# logo.net
KiCad netlist of a schematic drawn in EAGLE
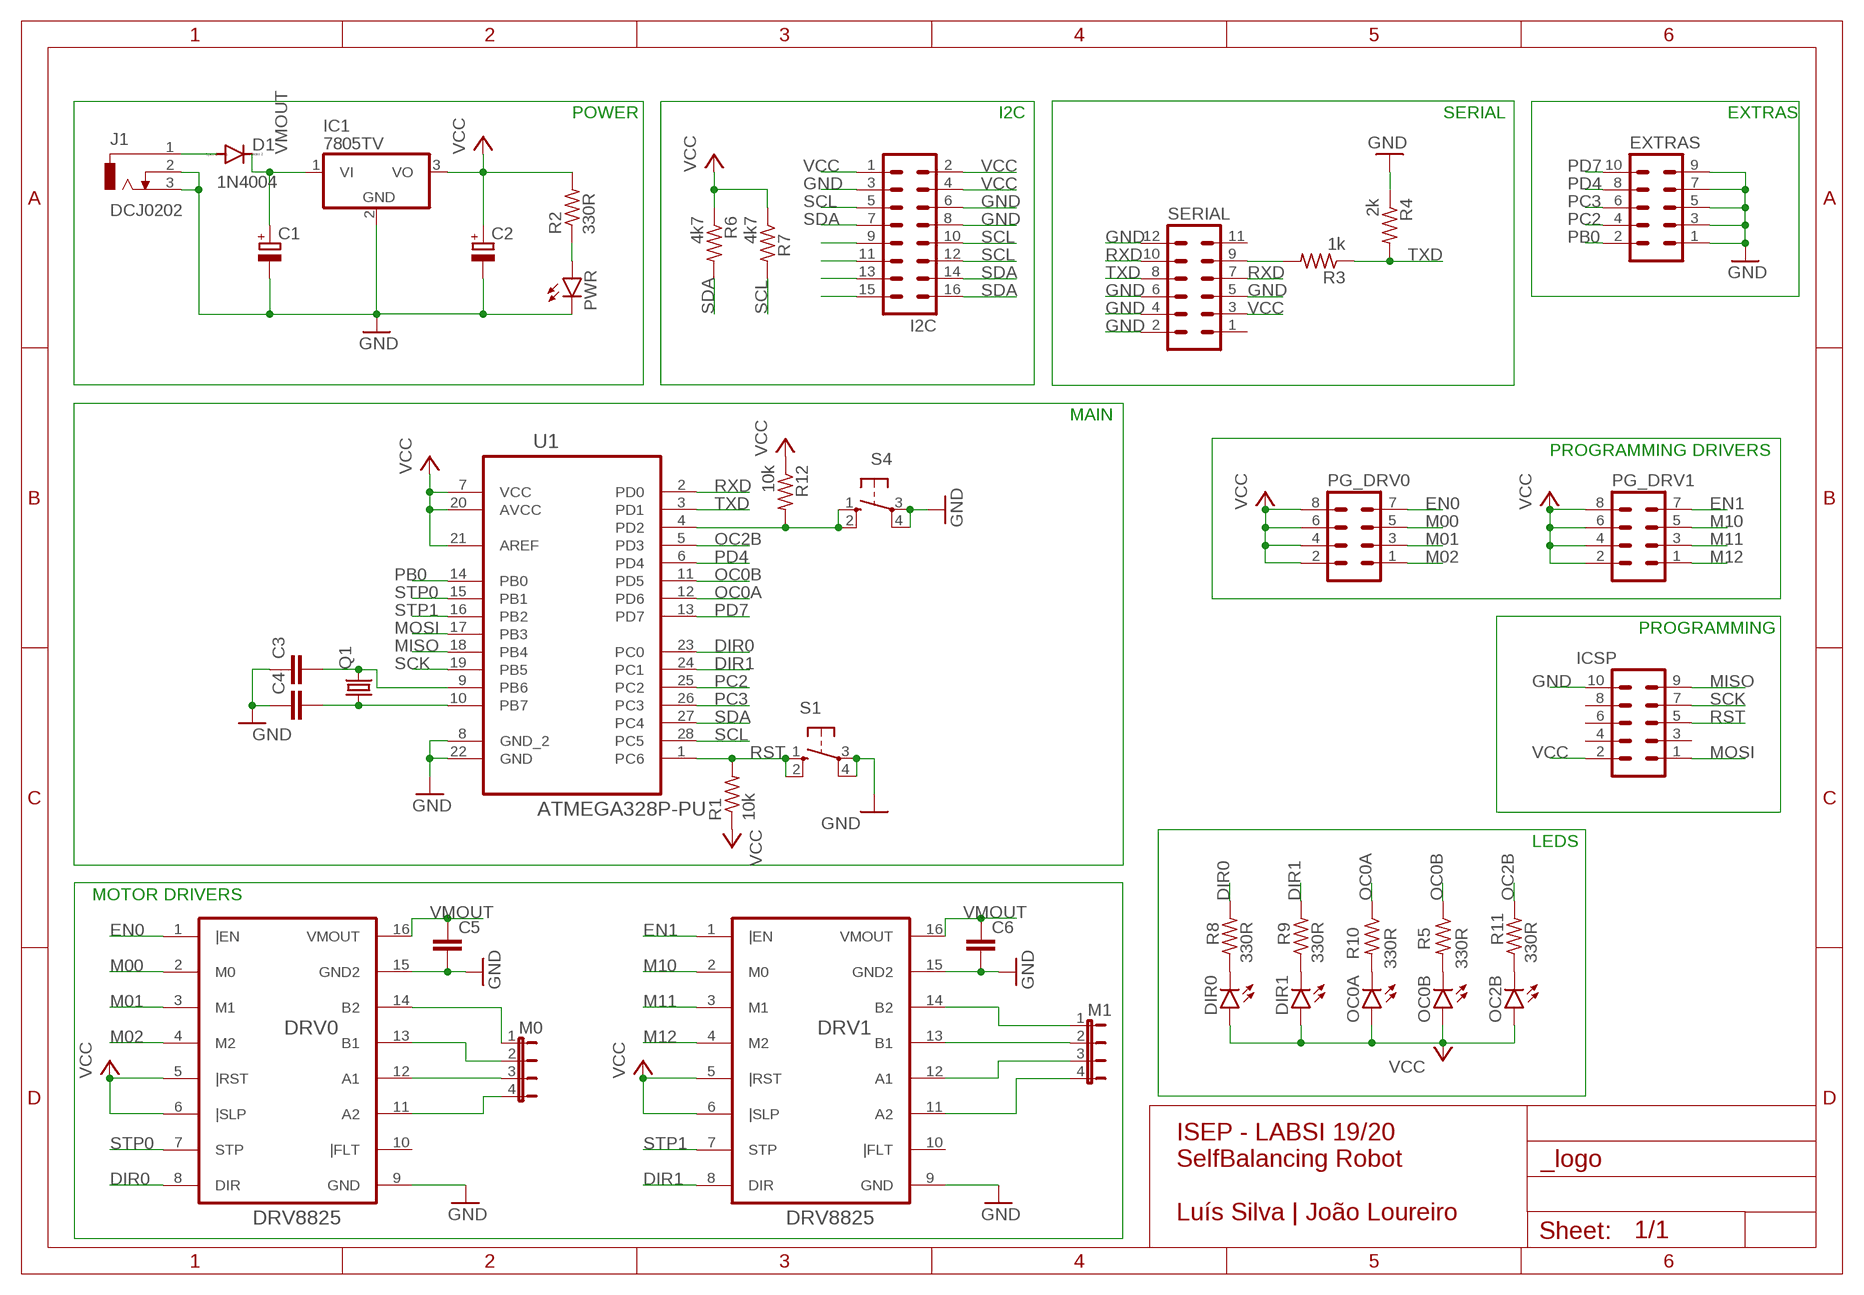
[diagram p0: schematic, sheet 1]

(export (version "E")
  (design (tool "Eeschema 10.0.6"))
  (components
    (comp (ref "C1")
      (value "CPOL-EUB45181A")
      (footprint "eagle-import:B45181A")
      (libsource (lib "eagle-import") (part "CPOL-EUB45181A"))
    )
    (comp (ref "C2")
      (value "CPOL-EUB45181A")
      (footprint "eagle-import:B45181A")
      (libsource (lib "eagle-import") (part "CPOL-EUB45181A"))
    )
    (comp (ref "C3")
      (value "C5/3")
      (footprint "eagle-import:C5B3")
      (libsource (lib "eagle-import") (part "C5/3"))
    )
    (comp (ref "C4")
      (value "C5/3")
      (footprint "eagle-import:C5B3")
      (libsource (lib "eagle-import") (part "C5/3"))
    )
    (comp (ref "C5")
      (value "C2.5/2")
      (footprint "eagle-import:C2.5-2")
      (libsource (lib "eagle-import") (part "C2.5/2"))
    )
    (comp (ref "C6")
      (value "C2.5/2")
      (footprint "eagle-import:C2.5-2")
      (libsource (lib "eagle-import") (part "C2.5/2"))
    )
    (comp (ref "D1")
      (value "1N4004")
      (footprint "eagle-import:DO41-10")
      (libsource (lib "eagle-import") (part "1N4004"))
    )
    (comp (ref "DIR0")
      (value "LED3MM")
      (footprint "eagle-import:LED3MM")
      (libsource (lib "eagle-import") (part "LED3MM"))
    )
    (comp (ref "DIR1")
      (value "LED3MM")
      (footprint "eagle-import:LED3MM")
      (libsource (lib "eagle-import") (part "LED3MM"))
    )
    (comp (ref "DRV0")
      (value "DRV8825")
      (footprint "eagle-import:DRV8825")
      (fields (field (name "MF") "Generic"))
      (libsource (lib "eagle-import") (part "DRV8825"))
    )
    (comp (ref "DRV1")
      (value "DRV8825")
      (footprint "eagle-import:DRV8825")
      (fields (field (name "MF") "Generic"))
      (libsource (lib "eagle-import") (part "DRV8825"))
    )
    (comp (ref "EXTRAS")
      (value "ML10")
      (footprint "eagle-import:ML10")
      (libsource (lib "eagle-import") (part "ML10"))
    )
    (comp (ref "I2C")
      (value "MA08-2")
      (footprint "eagle-import:MA08-2")
      (libsource (lib "eagle-import") (part "MA08-2"))
    )
    (comp (ref "IC1")
      (value "7805TV")
      (footprint "eagle-import:TO220V")
      (libsource (lib "eagle-import") (part "78TV05"))
    )
    (comp (ref "ICSP")
      (value "ML10")
      (footprint "eagle-import:ML10")
      (libsource (lib "eagle-import") (part "ML10"))
    )
    (comp (ref "J1")
      (value "DCJ0202")
      (footprint "eagle-import:DCJ0202")
      (libsource (lib "eagle-import") (part "DCJ0202"))
    )
    (comp (ref "M0")
      (value "JP4E")
      (footprint "eagle-import:JP4")
      (libsource (lib "eagle-import") (part "JP4E"))
    )
    (comp (ref "M1")
      (value "JP4E")
      (footprint "eagle-import:JP4")
      (libsource (lib "eagle-import") (part "JP4E"))
    )
    (comp (ref "OC0A")
      (value "LED3MM")
      (footprint "eagle-import:LED3MM")
      (libsource (lib "eagle-import") (part "LED3MM"))
    )
    (comp (ref "OC0B")
      (value "LED3MM")
      (footprint "eagle-import:LED3MM")
      (libsource (lib "eagle-import") (part "LED3MM"))
    )
    (comp (ref "OC2B")
      (value "LED3MM")
      (footprint "eagle-import:LED3MM")
      (libsource (lib "eagle-import") (part "LED3MM"))
    )
    (comp (ref "PG_DRV0")
      (value "MA04-2")
      (footprint "eagle-import:MA04-2")
      (libsource (lib "eagle-import") (part "MA04-2"))
    )
    (comp (ref "PG_DRV1")
      (value "MA04-2")
      (footprint "eagle-import:MA04-2")
      (libsource (lib "eagle-import") (part "MA04-2"))
    )
    (comp (ref "PWR")
      (value "LED3MM")
      (footprint "eagle-import:LED3MM")
      (libsource (lib "eagle-import") (part "LED3MM"))
    )
    (comp (ref "Q1")
      (value "CRYSTALHC49S")
      (footprint "eagle-import:HC49_S")
      (libsource (lib "eagle-import") (part "CRYSTALHC49S"))
    )
    (comp (ref "R1")
      (value "10k")
      (footprint "eagle-import:0207_10")
      (libsource (lib "eagle-import") (part "R-US_0207/10"))
    )
    (comp (ref "R2")
      (value "330R")
      (footprint "eagle-import:0207_10")
      (libsource (lib "eagle-import") (part "R-US_0207/10"))
    )
    (comp (ref "R3")
      (value "1k")
      (footprint "eagle-import:0207_10")
      (libsource (lib "eagle-import") (part "R-US_0207/10"))
    )
    (comp (ref "R4")
      (value "2k")
      (footprint "eagle-import:0207_10")
      (libsource (lib "eagle-import") (part "R-US_0207/10"))
    )
    (comp (ref "R5")
      (value "330R")
      (footprint "eagle-import:0207_10")
      (libsource (lib "eagle-import") (part "R-US_0207/10"))
    )
    (comp (ref "R6")
      (value "4k7")
      (footprint "eagle-import:0207_10")
      (libsource (lib "eagle-import") (part "R-US_0207/10"))
    )
    (comp (ref "R7")
      (value "4k7")
      (footprint "eagle-import:0207_10")
      (libsource (lib "eagle-import") (part "R-US_0207/10"))
    )
    (comp (ref "R8")
      (value "330R")
      (footprint "eagle-import:0207_10")
      (libsource (lib "eagle-import") (part "R-US_0207/10"))
    )
    (comp (ref "R9")
      (value "330R")
      (footprint "eagle-import:0207_10")
      (libsource (lib "eagle-import") (part "R-US_0207/10"))
    )
    (comp (ref "R10")
      (value "330R")
      (footprint "eagle-import:0207_10")
      (libsource (lib "eagle-import") (part "R-US_0207/10"))
    )
    (comp (ref "R11")
      (value "330R")
      (footprint "eagle-import:0207_10")
      (libsource (lib "eagle-import") (part "R-US_0207/10"))
    )
    (comp (ref "R12")
      (value "10k")
      (footprint "eagle-import:0207_10")
      (libsource (lib "eagle-import") (part "R-US_0207/10"))
    )
    (comp (ref "S1")
      (value "10-XX")
      (footprint "eagle-import:B3F-10XX")
      (fields (field (name "MPN") "B3F-1000"))
      (libsource (lib "eagle-import") (part "10-XX"))
    )
    (comp (ref "S4")
      (value "10-XX")
      (footprint "eagle-import:B3F-10XX")
      (fields (field (name "MPN") "B3F-1000"))
      (libsource (lib "eagle-import") (part "10-XX"))
    )
    (comp (ref "SERIAL")
      (value "MA06-2")
      (footprint "eagle-import:MA06-2")
      (libsource (lib "eagle-import") (part "MA06-2"))
    )
    (comp (ref "U1")
      (value "ATMEGA328P-PU")
      (footprint "eagle-import:DIP254P762X457-28")
      (fields (field (name "MF") "Generic"))
      (libsource (lib "eagle-import") (part "ATMEGA328P-PU"))
    )
  )
  (nets
    (net (code "1") (name "/DIR0") (class "Default")
      (node (ref "DRV0") (pin "8") (pinfunction "DIR_8") (pintype "bidirectional"))
      (node (ref "R8") (pin "2") (pinfunction "2_2") (pintype "passive"))
      (node (ref "U1") (pin "23") (pinfunction "PC0_23") (pintype "bidirectional"))
    )
    (net (code "2") (name "/DIR1") (class "Default")
      (node (ref "DRV1") (pin "8") (pinfunction "DIR_8") (pintype "bidirectional"))
      (node (ref "R9") (pin "2") (pinfunction "2_2") (pintype "passive"))
      (node (ref "U1") (pin "24") (pinfunction "PC1_24") (pintype "bidirectional"))
    )
    (net (code "3") (name "/EN0") (class "Default")
      (node (ref "DRV0") (pin "1") (pinfunction "|EN_1") (pintype "bidirectional"))
      (node (ref "PG_DRV0") (pin "7") (pinfunction "7_7") (pintype "passive"))
    )
    (net (code "4") (name "/EN1") (class "Default")
      (node (ref "DRV1") (pin "1") (pinfunction "|EN_1") (pintype "bidirectional"))
      (node (ref "PG_DRV1") (pin "7") (pinfunction "7_7") (pintype "passive"))
    )
    (net (code "5") (name "/M00") (class "Default")
      (node (ref "DRV0") (pin "2") (pinfunction "M0_2") (pintype "bidirectional"))
      (node (ref "PG_DRV0") (pin "5") (pinfunction "5_5") (pintype "passive"))
    )
    (net (code "6") (name "/M01") (class "Default")
      (node (ref "DRV0") (pin "3") (pinfunction "M1_3") (pintype "bidirectional"))
      (node (ref "PG_DRV0") (pin "3") (pinfunction "3_3") (pintype "passive"))
    )
    (net (code "7") (name "/M02") (class "Default")
      (node (ref "DRV0") (pin "4") (pinfunction "M2_4") (pintype "bidirectional"))
      (node (ref "PG_DRV0") (pin "1") (pinfunction "1_1") (pintype "passive"))
    )
    (net (code "8") (name "/M10") (class "Default")
      (node (ref "DRV1") (pin "2") (pinfunction "M0_2") (pintype "bidirectional"))
      (node (ref "PG_DRV1") (pin "5") (pinfunction "5_5") (pintype "passive"))
    )
    (net (code "9") (name "/M11") (class "Default")
      (node (ref "DRV1") (pin "3") (pinfunction "M1_3") (pintype "bidirectional"))
      (node (ref "PG_DRV1") (pin "3") (pinfunction "3_3") (pintype "passive"))
    )
    (net (code "10") (name "/M12") (class "Default")
      (node (ref "DRV1") (pin "4") (pinfunction "M2_4") (pintype "bidirectional"))
      (node (ref "PG_DRV1") (pin "1") (pinfunction "1_1") (pintype "passive"))
    )
    (net (code "11") (name "/MISO") (class "Default")
      (node (ref "ICSP") (pin "9") (pinfunction "9_9") (pintype "passive"))
      (node (ref "U1") (pin "18") (pinfunction "PB4_18") (pintype "bidirectional"))
    )
    (net (code "12") (name "/MOSI") (class "Default")
      (node (ref "ICSP") (pin "1") (pinfunction "1_1") (pintype "passive"))
      (node (ref "U1") (pin "17") (pinfunction "PB3_17") (pintype "bidirectional"))
    )
    (net (code "13") (name "/OC0A") (class "Default")
      (node (ref "R10") (pin "1") (pinfunction "1_1") (pintype "passive"))
      (node (ref "U1") (pin "12") (pinfunction "PD6_12") (pintype "bidirectional"))
    )
    (net (code "14") (name "/OC0B") (class "Default")
      (node (ref "R5") (pin "1") (pinfunction "1_1") (pintype "passive"))
      (node (ref "U1") (pin "11") (pinfunction "PD5_11") (pintype "bidirectional"))
    )
    (net (code "15") (name "/OC2B") (class "Default")
      (node (ref "R11") (pin "2") (pinfunction "2_2") (pintype "passive"))
      (node (ref "U1") (pin "5") (pinfunction "PD3_5") (pintype "bidirectional"))
    )
    (net (code "16") (name "/PB0") (class "Default")
      (node (ref "EXTRAS") (pin "2") (pinfunction "2_2") (pintype "passive"))
      (node (ref "U1") (pin "14") (pinfunction "PB0_14") (pintype "bidirectional"))
    )
    (net (code "17") (name "/PC2") (class "Default")
      (node (ref "EXTRAS") (pin "4") (pinfunction "4_4") (pintype "passive"))
      (node (ref "U1") (pin "25") (pinfunction "PC2_25") (pintype "bidirectional"))
    )
    (net (code "18") (name "/PC3") (class "Default")
      (node (ref "EXTRAS") (pin "6") (pinfunction "6_6") (pintype "passive"))
      (node (ref "U1") (pin "26") (pinfunction "PC3_26") (pintype "bidirectional"))
    )
    (net (code "19") (name "/PD4") (class "Default")
      (node (ref "EXTRAS") (pin "8") (pinfunction "8_8") (pintype "passive"))
      (node (ref "U1") (pin "6") (pinfunction "PD4_6") (pintype "bidirectional"))
    )
    (net (code "20") (name "/PD7") (class "Default")
      (node (ref "EXTRAS") (pin "10") (pinfunction "10_10") (pintype "passive"))
      (node (ref "U1") (pin "13") (pinfunction "PD7_13") (pintype "bidirectional"))
    )
    (net (code "21") (name "/RST") (class "Default")
      (node (ref "ICSP") (pin "5") (pinfunction "5_5") (pintype "passive"))
      (node (ref "R1") (pin "2") (pinfunction "2_2") (pintype "passive"))
      (node (ref "S1") (pin "1") (pinfunction "S_1") (pintype "passive"))
      (node (ref "S1") (pin "2") (pinfunction "S1_2") (pintype "passive"))
      (node (ref "U1") (pin "1") (pinfunction "PC6_1") (pintype "bidirectional"))
    )
    (net (code "22") (name "/RXD") (class "Default")
      (node (ref "SERIAL") (pin "10") (pinfunction "10_10") (pintype "passive"))
      (node (ref "SERIAL") (pin "7") (pinfunction "7_7") (pintype "passive"))
      (node (ref "U1") (pin "2") (pinfunction "PD0_2") (pintype "bidirectional"))
    )
    (net (code "23") (name "/SCK") (class "Default")
      (node (ref "ICSP") (pin "7") (pinfunction "7_7") (pintype "passive"))
      (node (ref "U1") (pin "19") (pinfunction "PB5_19") (pintype "bidirectional"))
    )
    (net (code "24") (name "/SCL") (class "Default")
      (node (ref "I2C") (pin "10") (pinfunction "10_10") (pintype "passive"))
      (node (ref "I2C") (pin "12") (pinfunction "12_12") (pintype "passive"))
      (node (ref "I2C") (pin "5") (pinfunction "5_5") (pintype "passive"))
      (node (ref "R7") (pin "2") (pinfunction "2_2") (pintype "passive"))
      (node (ref "U1") (pin "28") (pinfunction "PC5_28") (pintype "bidirectional"))
    )
    (net (code "25") (name "/SDA") (class "Default")
      (node (ref "I2C") (pin "14") (pinfunction "14_14") (pintype "passive"))
      (node (ref "I2C") (pin "16") (pinfunction "16_16") (pintype "passive"))
      (node (ref "I2C") (pin "7") (pinfunction "7_7") (pintype "passive"))
      (node (ref "R6") (pin "2") (pinfunction "2_2") (pintype "passive"))
      (node (ref "U1") (pin "27") (pinfunction "PC4_27") (pintype "bidirectional"))
    )
    (net (code "26") (name "/STP0") (class "Default")
      (node (ref "DRV0") (pin "7") (pinfunction "STP_7") (pintype "bidirectional"))
      (node (ref "U1") (pin "15") (pinfunction "PB1_15") (pintype "bidirectional"))
    )
    (net (code "27") (name "/STP1") (class "Default")
      (node (ref "DRV1") (pin "7") (pinfunction "STP_7") (pintype "bidirectional"))
      (node (ref "U1") (pin "16") (pinfunction "PB2_16") (pintype "bidirectional"))
    )
    (net (code "28") (name "/TXD") (class "Default")
      (node (ref "R3") (pin "1") (pinfunction "1_1") (pintype "passive"))
      (node (ref "R4") (pin "2") (pinfunction "2_2") (pintype "passive"))
      (node (ref "SERIAL") (pin "8") (pinfunction "8_8") (pintype "passive"))
      (node (ref "U1") (pin "3") (pinfunction "PD1_3") (pintype "bidirectional"))
    )
    (net (code "29") (name "/VMOUT") (class "Default")
      (node (ref "C1") (pin "+") (pinfunction "+_+") (pintype "passive"))
      (node (ref "C5") (pin "1") (pinfunction "1_1") (pintype "passive"))
      (node (ref "C6") (pin "1") (pinfunction "1_1") (pintype "passive"))
      (node (ref "D1") (pin "C") (pinfunction "C_C") (pintype "passive"))
      (node (ref "DRV0") (pin "16") (pinfunction "VMOUT_16") (pintype "bidirectional"))
      (node (ref "DRV1") (pin "16") (pinfunction "VMOUT_16") (pintype "bidirectional"))
      (node (ref "IC1") (pin "1") (pinfunction "VI_1") (pintype "input"))
    )
    (net (code "30") (name "GND") (class "Default")
      (node (ref "C1") (pin "-") (pinfunction "-_-") (pintype "passive"))
      (node (ref "C2") (pin "-") (pinfunction "-_-") (pintype "passive"))
      (node (ref "C3") (pin "1") (pinfunction "1_1") (pintype "passive"))
      (node (ref "C4") (pin "1") (pinfunction "1_1") (pintype "passive"))
      (node (ref "C5") (pin "2") (pinfunction "2_2") (pintype "passive"))
      (node (ref "C6") (pin "2") (pinfunction "2_2") (pintype "passive"))
      (node (ref "DRV0") (pin "15") (pinfunction "GND2_15") (pintype "bidirectional"))
      (node (ref "DRV0") (pin "9") (pinfunction "GND_9") (pintype "bidirectional"))
      (node (ref "DRV1") (pin "15") (pinfunction "GND2_15") (pintype "bidirectional"))
      (node (ref "DRV1") (pin "9") (pinfunction "GND_9") (pintype "bidirectional"))
      (node (ref "EXTRAS") (pin "1") (pinfunction "1_1") (pintype "passive"))
      (node (ref "EXTRAS") (pin "3") (pinfunction "3_3") (pintype "passive"))
      (node (ref "EXTRAS") (pin "5") (pinfunction "5_5") (pintype "passive"))
      (node (ref "EXTRAS") (pin "7") (pinfunction "7_7") (pintype "passive"))
      (node (ref "EXTRAS") (pin "9") (pinfunction "9_9") (pintype "passive"))
      (node (ref "I2C") (pin "3") (pinfunction "3_3") (pintype "passive"))
      (node (ref "I2C") (pin "6") (pinfunction "6_6") (pintype "passive"))
      (node (ref "I2C") (pin "8") (pinfunction "8_8") (pintype "passive"))
      (node (ref "IC1") (pin "2") (pinfunction "GND_2") (pintype "passive"))
      (node (ref "ICSP") (pin "10") (pinfunction "10_10") (pintype "passive"))
      (node (ref "J1") (pin "2") (pinfunction "2_2") (pintype "passive"))
      (node (ref "J1") (pin "3") (pinfunction "3_3") (pintype "passive"))
      (node (ref "PWR") (pin "K") (pinfunction "C_K") (pintype "passive"))
      (node (ref "R4") (pin "1") (pinfunction "1_1") (pintype "passive"))
      (node (ref "S1") (pin "3") (pinfunction "P_3") (pintype "passive"))
      (node (ref "S1") (pin "4") (pinfunction "P1_4") (pintype "passive"))
      (node (ref "S4") (pin "3") (pinfunction "P_3") (pintype "passive"))
      (node (ref "S4") (pin "4") (pinfunction "P1_4") (pintype "passive"))
      (node (ref "SERIAL") (pin "12") (pinfunction "12_12") (pintype "passive"))
      (node (ref "SERIAL") (pin "2") (pinfunction "2_2") (pintype "passive"))
      (node (ref "SERIAL") (pin "4") (pinfunction "4_4") (pintype "passive"))
      (node (ref "SERIAL") (pin "5") (pinfunction "5_5") (pintype "passive"))
      (node (ref "SERIAL") (pin "6") (pinfunction "6_6") (pintype "passive"))
      (node (ref "U1") (pin "22") (pinfunction "GND_22") (pintype "passive"))
      (node (ref "U1") (pin "8") (pinfunction "GND_2_8") (pintype "passive"))
    )
    (net (code "31") (name "Net-(D1-PadA)") (class "Default")
      (node (ref "D1") (pin "A") (pinfunction "A_A") (pintype "passive"))
      (node (ref "J1") (pin "1") (pinfunction "1_1") (pintype "passive"))
    )
    (net (code "32") (name "Net-(DIR0-C)") (class "Default")
      (node (ref "DIR0") (pin "K") (pinfunction "C_K") (pintype "passive"))
      (node (ref "R8") (pin "1") (pinfunction "1_1") (pintype "passive"))
    )
    (net (code "33") (name "Net-(DIR1-C)") (class "Default")
      (node (ref "DIR1") (pin "K") (pinfunction "C_K") (pintype "passive"))
      (node (ref "R9") (pin "1") (pinfunction "1_1") (pintype "passive"))
    )
    (net (code "34") (name "Net-(DRV0-A1)") (class "Default")
      (node (ref "DRV0") (pin "12") (pinfunction "A1_12") (pintype "bidirectional"))
      (node (ref "M0") (pin "3") (pinfunction "3_3") (pintype "passive"))
    )
    (net (code "35") (name "Net-(DRV0-A2)") (class "Default")
      (node (ref "DRV0") (pin "11") (pinfunction "A2_11") (pintype "bidirectional"))
      (node (ref "M0") (pin "4") (pinfunction "4_4") (pintype "passive"))
    )
    (net (code "36") (name "Net-(DRV0-B1)") (class "Default")
      (node (ref "DRV0") (pin "13") (pinfunction "B1_13") (pintype "bidirectional"))
      (node (ref "M0") (pin "2") (pinfunction "2_2") (pintype "passive"))
    )
    (net (code "37") (name "Net-(DRV0-B2)") (class "Default")
      (node (ref "DRV0") (pin "14") (pinfunction "B2_14") (pintype "bidirectional"))
      (node (ref "M0") (pin "1") (pinfunction "1_1") (pintype "passive"))
    )
    (net (code "38") (name "Net-(DRV1-A1)") (class "Default")
      (node (ref "DRV1") (pin "12") (pinfunction "A1_12") (pintype "bidirectional"))
      (node (ref "M1") (pin "3") (pinfunction "3_3") (pintype "passive"))
    )
    (net (code "39") (name "Net-(DRV1-A2)") (class "Default")
      (node (ref "DRV1") (pin "11") (pinfunction "A2_11") (pintype "bidirectional"))
      (node (ref "M1") (pin "4") (pinfunction "4_4") (pintype "passive"))
    )
    (net (code "40") (name "Net-(DRV1-B1)") (class "Default")
      (node (ref "DRV1") (pin "13") (pinfunction "B1_13") (pintype "bidirectional"))
      (node (ref "M1") (pin "2") (pinfunction "2_2") (pintype "passive"))
    )
    (net (code "41") (name "Net-(DRV1-B2)") (class "Default")
      (node (ref "DRV1") (pin "14") (pinfunction "B2_14") (pintype "bidirectional"))
      (node (ref "M1") (pin "1") (pinfunction "1_1") (pintype "passive"))
    )
    (net (code "42") (name "Net-(OC0A-C)") (class "Default")
      (node (ref "OC0A") (pin "K") (pinfunction "C_K") (pintype "passive"))
      (node (ref "R10") (pin "2") (pinfunction "2_2") (pintype "passive"))
    )
    (net (code "43") (name "Net-(OC0B-C)") (class "Default")
      (node (ref "OC0B") (pin "K") (pinfunction "C_K") (pintype "passive"))
      (node (ref "R5") (pin "2") (pinfunction "2_2") (pintype "passive"))
    )
    (net (code "44") (name "Net-(OC2B-C)") (class "Default")
      (node (ref "OC2B") (pin "K") (pinfunction "C_K") (pintype "passive"))
      (node (ref "R11") (pin "1") (pinfunction "1_1") (pintype "passive"))
    )
    (net (code "45") (name "Net-(PWR-PadA)") (class "Default")
      (node (ref "PWR") (pin "A") (pinfunction "A_A") (pintype "passive"))
      (node (ref "R2") (pin "1") (pinfunction "1_1") (pintype "passive"))
    )
    (net (code "46") (name "Net-(R3-Pad2)") (class "Default")
      (node (ref "R3") (pin "2") (pinfunction "2_2") (pintype "passive"))
      (node (ref "SERIAL") (pin "9") (pinfunction "9_9") (pintype "passive"))
    )
    (net (code "47") (name "Net-(S4-S)") (class "Default")
      (node (ref "R12") (pin "2") (pinfunction "2_2") (pintype "passive"))
      (node (ref "S4") (pin "1") (pinfunction "S_1") (pintype "passive"))
      (node (ref "S4") (pin "2") (pinfunction "S1_2") (pintype "passive"))
      (node (ref "U1") (pin "4") (pinfunction "PD2_4") (pintype "bidirectional"))
    )
    (net (code "48") (name "Net-(U1-PB6)") (class "Default")
      (node (ref "C3") (pin "2") (pinfunction "2_2") (pintype "passive"))
      (node (ref "Q1") (pin "2") (pinfunction "2_2") (pintype "passive"))
      (node (ref "U1") (pin "9") (pinfunction "PB6_9") (pintype "bidirectional"))
    )
    (net (code "49") (name "Net-(U1-PB7)") (class "Default")
      (node (ref "C4") (pin "2") (pinfunction "2_2") (pintype "passive"))
      (node (ref "Q1") (pin "1") (pinfunction "1_1") (pintype "passive"))
      (node (ref "U1") (pin "10") (pinfunction "PB7_10") (pintype "bidirectional"))
    )
    (net (code "50") (name "VCC") (class "Default")
      (node (ref "C2") (pin "+") (pinfunction "+_+") (pintype "passive"))
      (node (ref "DIR0") (pin "A") (pinfunction "A_A") (pintype "passive"))
      (node (ref "DIR1") (pin "A") (pinfunction "A_A") (pintype "passive"))
      (node (ref "DRV0") (pin "5") (pinfunction "|RST_5") (pintype "bidirectional"))
      (node (ref "DRV0") (pin "6") (pinfunction "|SLP_6") (pintype "bidirectional"))
      (node (ref "DRV1") (pin "5") (pinfunction "|RST_5") (pintype "bidirectional"))
      (node (ref "DRV1") (pin "6") (pinfunction "|SLP_6") (pintype "bidirectional"))
      (node (ref "I2C") (pin "1") (pinfunction "1_1") (pintype "passive"))
      (node (ref "I2C") (pin "2") (pinfunction "2_2") (pintype "passive"))
      (node (ref "I2C") (pin "4") (pinfunction "4_4") (pintype "passive"))
      (node (ref "IC1") (pin "3") (pinfunction "VO_3") (pintype "passive"))
      (node (ref "ICSP") (pin "2") (pinfunction "2_2") (pintype "passive"))
      (node (ref "OC0A") (pin "A") (pinfunction "A_A") (pintype "passive"))
      (node (ref "OC0B") (pin "A") (pinfunction "A_A") (pintype "passive"))
      (node (ref "OC2B") (pin "A") (pinfunction "A_A") (pintype "passive"))
      (node (ref "PG_DRV0") (pin "2") (pinfunction "2_2") (pintype "passive"))
      (node (ref "PG_DRV0") (pin "4") (pinfunction "4_4") (pintype "passive"))
      (node (ref "PG_DRV0") (pin "6") (pinfunction "6_6") (pintype "passive"))
      (node (ref "PG_DRV0") (pin "8") (pinfunction "8_8") (pintype "passive"))
      (node (ref "PG_DRV1") (pin "2") (pinfunction "2_2") (pintype "passive"))
      (node (ref "PG_DRV1") (pin "4") (pinfunction "4_4") (pintype "passive"))
      (node (ref "PG_DRV1") (pin "6") (pinfunction "6_6") (pintype "passive"))
      (node (ref "PG_DRV1") (pin "8") (pinfunction "8_8") (pintype "passive"))
      (node (ref "R1") (pin "1") (pinfunction "1_1") (pintype "passive"))
      (node (ref "R12") (pin "1") (pinfunction "1_1") (pintype "passive"))
      (node (ref "R2") (pin "2") (pinfunction "2_2") (pintype "passive"))
      (node (ref "R6") (pin "1") (pinfunction "1_1") (pintype "passive"))
      (node (ref "R7") (pin "1") (pinfunction "1_1") (pintype "passive"))
      (node (ref "SERIAL") (pin "3") (pinfunction "3_3") (pintype "passive"))
      (node (ref "U1") (pin "20") (pinfunction "AVCC_20") (pintype "power_in"))
      (node (ref "U1") (pin "21") (pinfunction "AREF_21") (pintype "input"))
      (node (ref "U1") (pin "7") (pinfunction "VCC_7") (pintype "power_in"))
    )
    (net (code "51") (name "unconnected-(DRV0-|FLT-Pad10)") (class "Default")
      (node (ref "DRV0") (pin "10") (pinfunction "|FLT_10") (pintype "bidirectional"))
    )
    (net (code "52") (name "unconnected-(DRV1-|FLT-Pad10)") (class "Default")
      (node (ref "DRV1") (pin "10") (pinfunction "|FLT_10") (pintype "bidirectional"))
    )
    (net (code "53") (name "unconnected-(I2C-Pad9)") (class "Default")
      (node (ref "I2C") (pin "9") (pinfunction "9_9") (pintype "passive"))
    )
    (net (code "54") (name "unconnected-(I2C-Pad11)") (class "Default")
      (node (ref "I2C") (pin "11") (pinfunction "11_11") (pintype "passive"))
    )
    (net (code "55") (name "unconnected-(I2C-Pad13)") (class "Default")
      (node (ref "I2C") (pin "13") (pinfunction "13_13") (pintype "passive"))
    )
    (net (code "56") (name "unconnected-(I2C-Pad15)") (class "Default")
      (node (ref "I2C") (pin "15") (pinfunction "15_15") (pintype "passive"))
    )
    (net (code "57") (name "unconnected-(ICSP-Pad3)") (class "Default")
      (node (ref "ICSP") (pin "3") (pinfunction "3_3") (pintype "passive"))
    )
    (net (code "58") (name "unconnected-(ICSP-Pad4)") (class "Default")
      (node (ref "ICSP") (pin "4") (pinfunction "4_4") (pintype "passive"))
    )
    (net (code "59") (name "unconnected-(ICSP-Pad6)") (class "Default")
      (node (ref "ICSP") (pin "6") (pinfunction "6_6") (pintype "passive"))
    )
    (net (code "60") (name "unconnected-(ICSP-Pad8)") (class "Default")
      (node (ref "ICSP") (pin "8") (pinfunction "8_8") (pintype "passive"))
    )
    (net (code "61") (name "unconnected-(SERIAL-Pad1)") (class "Default")
      (node (ref "SERIAL") (pin "1") (pinfunction "1_1") (pintype "passive"))
    )
    (net (code "62") (name "unconnected-(SERIAL-Pad11)") (class "Default")
      (node (ref "SERIAL") (pin "11") (pinfunction "11_11") (pintype "passive"))
    )
  )
)
